# node.net
KiCad netlist of a schematic drawn in EAGLE
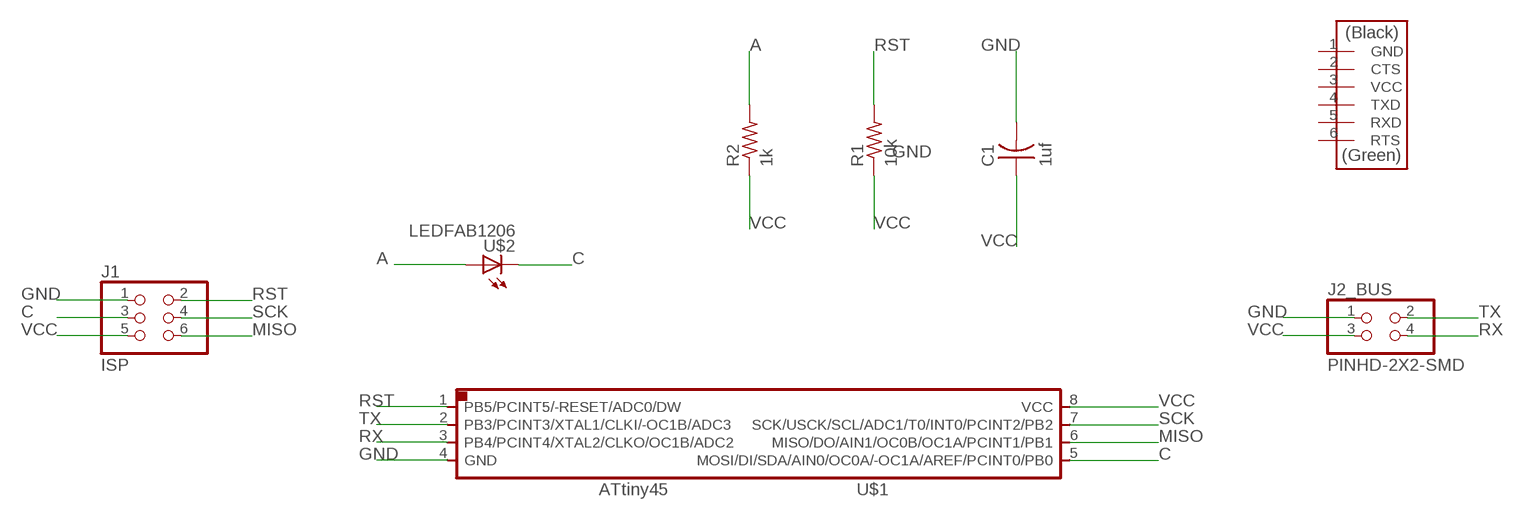
[diagram p0: schematic, sheet 1]

(export (version "E")
  (design (tool "Eeschema 10.0.6"))
  (components
    (comp (ref "C1")
      (value "1uf")
      (footprint "eagle-import:C1206FAB")
      (libsource (lib "eagle-import") (part "CAP-US1206FAB"))
    )
    (comp (ref "J1")
      (value "ISP")
      (footprint "eagle-import:2X03SMD")
      (libsource (lib "eagle-import") (part "PINHD-2X3-SMD"))
    )
    (comp (ref "J2_BUS")
      (value "PINHD-2X2-SMD")
      (footprint "eagle-import:2X02SMD")
      (libsource (lib "eagle-import") (part "PINHD-2X2-SMD"))
    )
    (comp (ref "R1")
      (value "10k")
      (footprint "eagle-import:R1206FAB")
      (libsource (lib "eagle-import") (part "RES-US1206FAB"))
    )
    (comp (ref "R2")
      (value "1k")
      (footprint "eagle-import:R1206FAB")
      (libsource (lib "eagle-import") (part "RES-US1206FAB"))
    )
    (comp (ref "U$1")
      (value "ATTINY45SI")
      (footprint "eagle-import:SOIC8")
      (libsource (lib "eagle-import") (part "ATTINY45SI"))
    )
    (comp (ref "U$2")
      (value "LEDFAB1206")
      (footprint "eagle-import:LED1206FAB")
      (libsource (lib "eagle-import") (part "LEDFAB1206"))
    )
    (comp (ref "U$3")
      (value "FTDI-SMD-HEADER")
      (footprint "eagle-import:1X06SMD")
      (libsource (lib "eagle-import") (part "FTDI-SMD-HEADER"))
    )
  )
  (nets
    (net (code "1") (name "/A") (class "Default")
      (node (ref "R2") (pin "2") (pinfunction "2_2") (pintype "passive"))
      (node (ref "U$2") (pin "1") (pinfunction "A_1") (pintype "passive"))
    )
    (net (code "2") (name "/C") (class "Default")
      (node (ref "J1") (pin "3") (pinfunction "3_3") (pintype "passive"))
      (node (ref "U$1") (pin "5") (pinfunction "MOSI/DI/SDA/AIN0/OC0A/-OC1A/AREF/PCINT0/PB0_5") (pintype "bidirectional"))
      (node (ref "U$2") (pin "2") (pinfunction "C_2") (pintype "passive"))
    )
    (net (code "3") (name "/GND") (class "Default")
      (node (ref "C1") (pin "2") (pinfunction "2_2") (pintype "passive"))
      (node (ref "J1") (pin "1") (pinfunction "1_1") (pintype "passive"))
      (node (ref "J2_BUS") (pin "1") (pinfunction "1_1") (pintype "passive"))
      (node (ref "U$1") (pin "4") (pinfunction "GND_4") (pintype "bidirectional"))
    )
    (net (code "4") (name "/MISO") (class "Default")
      (node (ref "J1") (pin "6") (pinfunction "6_6") (pintype "passive"))
      (node (ref "U$1") (pin "6") (pinfunction "MISO/DO/AIN1/OC0B/OC1A/PCINT1/PB1_6") (pintype "bidirectional"))
    )
    (net (code "5") (name "/RST") (class "Default")
      (node (ref "J1") (pin "2") (pinfunction "2_2") (pintype "passive"))
      (node (ref "R1") (pin "2") (pinfunction "2_2") (pintype "passive"))
      (node (ref "U$1") (pin "1") (pinfunction "PB5/PCINT5/-RESET/ADC0/DW_1") (pintype "bidirectional"))
    )
    (net (code "6") (name "/RX") (class "Default")
      (node (ref "J2_BUS") (pin "4") (pinfunction "4_4") (pintype "passive"))
      (node (ref "U$1") (pin "3") (pinfunction "PB4/PCINT4/XTAL2/CLKO/OC1B/ADC2_3") (pintype "bidirectional"))
    )
    (net (code "7") (name "/SCK") (class "Default")
      (node (ref "J1") (pin "4") (pinfunction "4_4") (pintype "passive"))
      (node (ref "U$1") (pin "7") (pinfunction "SCK/USCK/SCL/ADC1/T0/INT0/PCINT2/PB2_7") (pintype "bidirectional"))
    )
    (net (code "8") (name "/TX") (class "Default")
      (node (ref "J2_BUS") (pin "2") (pinfunction "2_2") (pintype "passive"))
      (node (ref "U$1") (pin "2") (pinfunction "PB3/PCINT3/XTAL1/CLKI/-OC1B/ADC3_2") (pintype "bidirectional"))
    )
    (net (code "9") (name "/VCC") (class "Default")
      (node (ref "C1") (pin "1") (pinfunction "1_1") (pintype "passive"))
      (node (ref "J1") (pin "5") (pinfunction "5_5") (pintype "passive"))
      (node (ref "J2_BUS") (pin "3") (pinfunction "3_3") (pintype "passive"))
      (node (ref "R1") (pin "1") (pinfunction "1_1") (pintype "passive"))
      (node (ref "R2") (pin "1") (pinfunction "1_1") (pintype "passive"))
      (node (ref "U$1") (pin "8") (pinfunction "VCC_8") (pintype "bidirectional"))
    )
    (net (code "10") (name "unconnected-(U$3-CTS-Pad2)") (class "Default")
      (node (ref "U$3") (pin "2") (pinfunction "CTS_2") (pintype "bidirectional"))
    )
    (net (code "11") (name "unconnected-(U$3-GND-Pad1)") (class "Default")
      (node (ref "U$3") (pin "1") (pinfunction "GND_1") (pintype "bidirectional"))
    )
    (net (code "12") (name "unconnected-(U$3-RTS-Pad6)") (class "Default")
      (node (ref "U$3") (pin "6") (pinfunction "RTS_6") (pintype "bidirectional"))
    )
    (net (code "13") (name "unconnected-(U$3-RXD-Pad5)") (class "Default")
      (node (ref "U$3") (pin "5") (pinfunction "RXD_5") (pintype "bidirectional"))
    )
    (net (code "14") (name "unconnected-(U$3-TXD-Pad4)") (class "Default")
      (node (ref "U$3") (pin "4") (pinfunction "TXD_4") (pintype "bidirectional"))
    )
    (net (code "15") (name "unconnected-(U$3-VCC-Pad3)") (class "Default")
      (node (ref "U$3") (pin "3") (pinfunction "VCC_3") (pintype "bidirectional"))
    )
  )
)
